# ProDocument_RFID-ARDUINO-FABLAB-BG_2024-.net
KiCad netlist of a schematic drawn in EasyEDA Pro
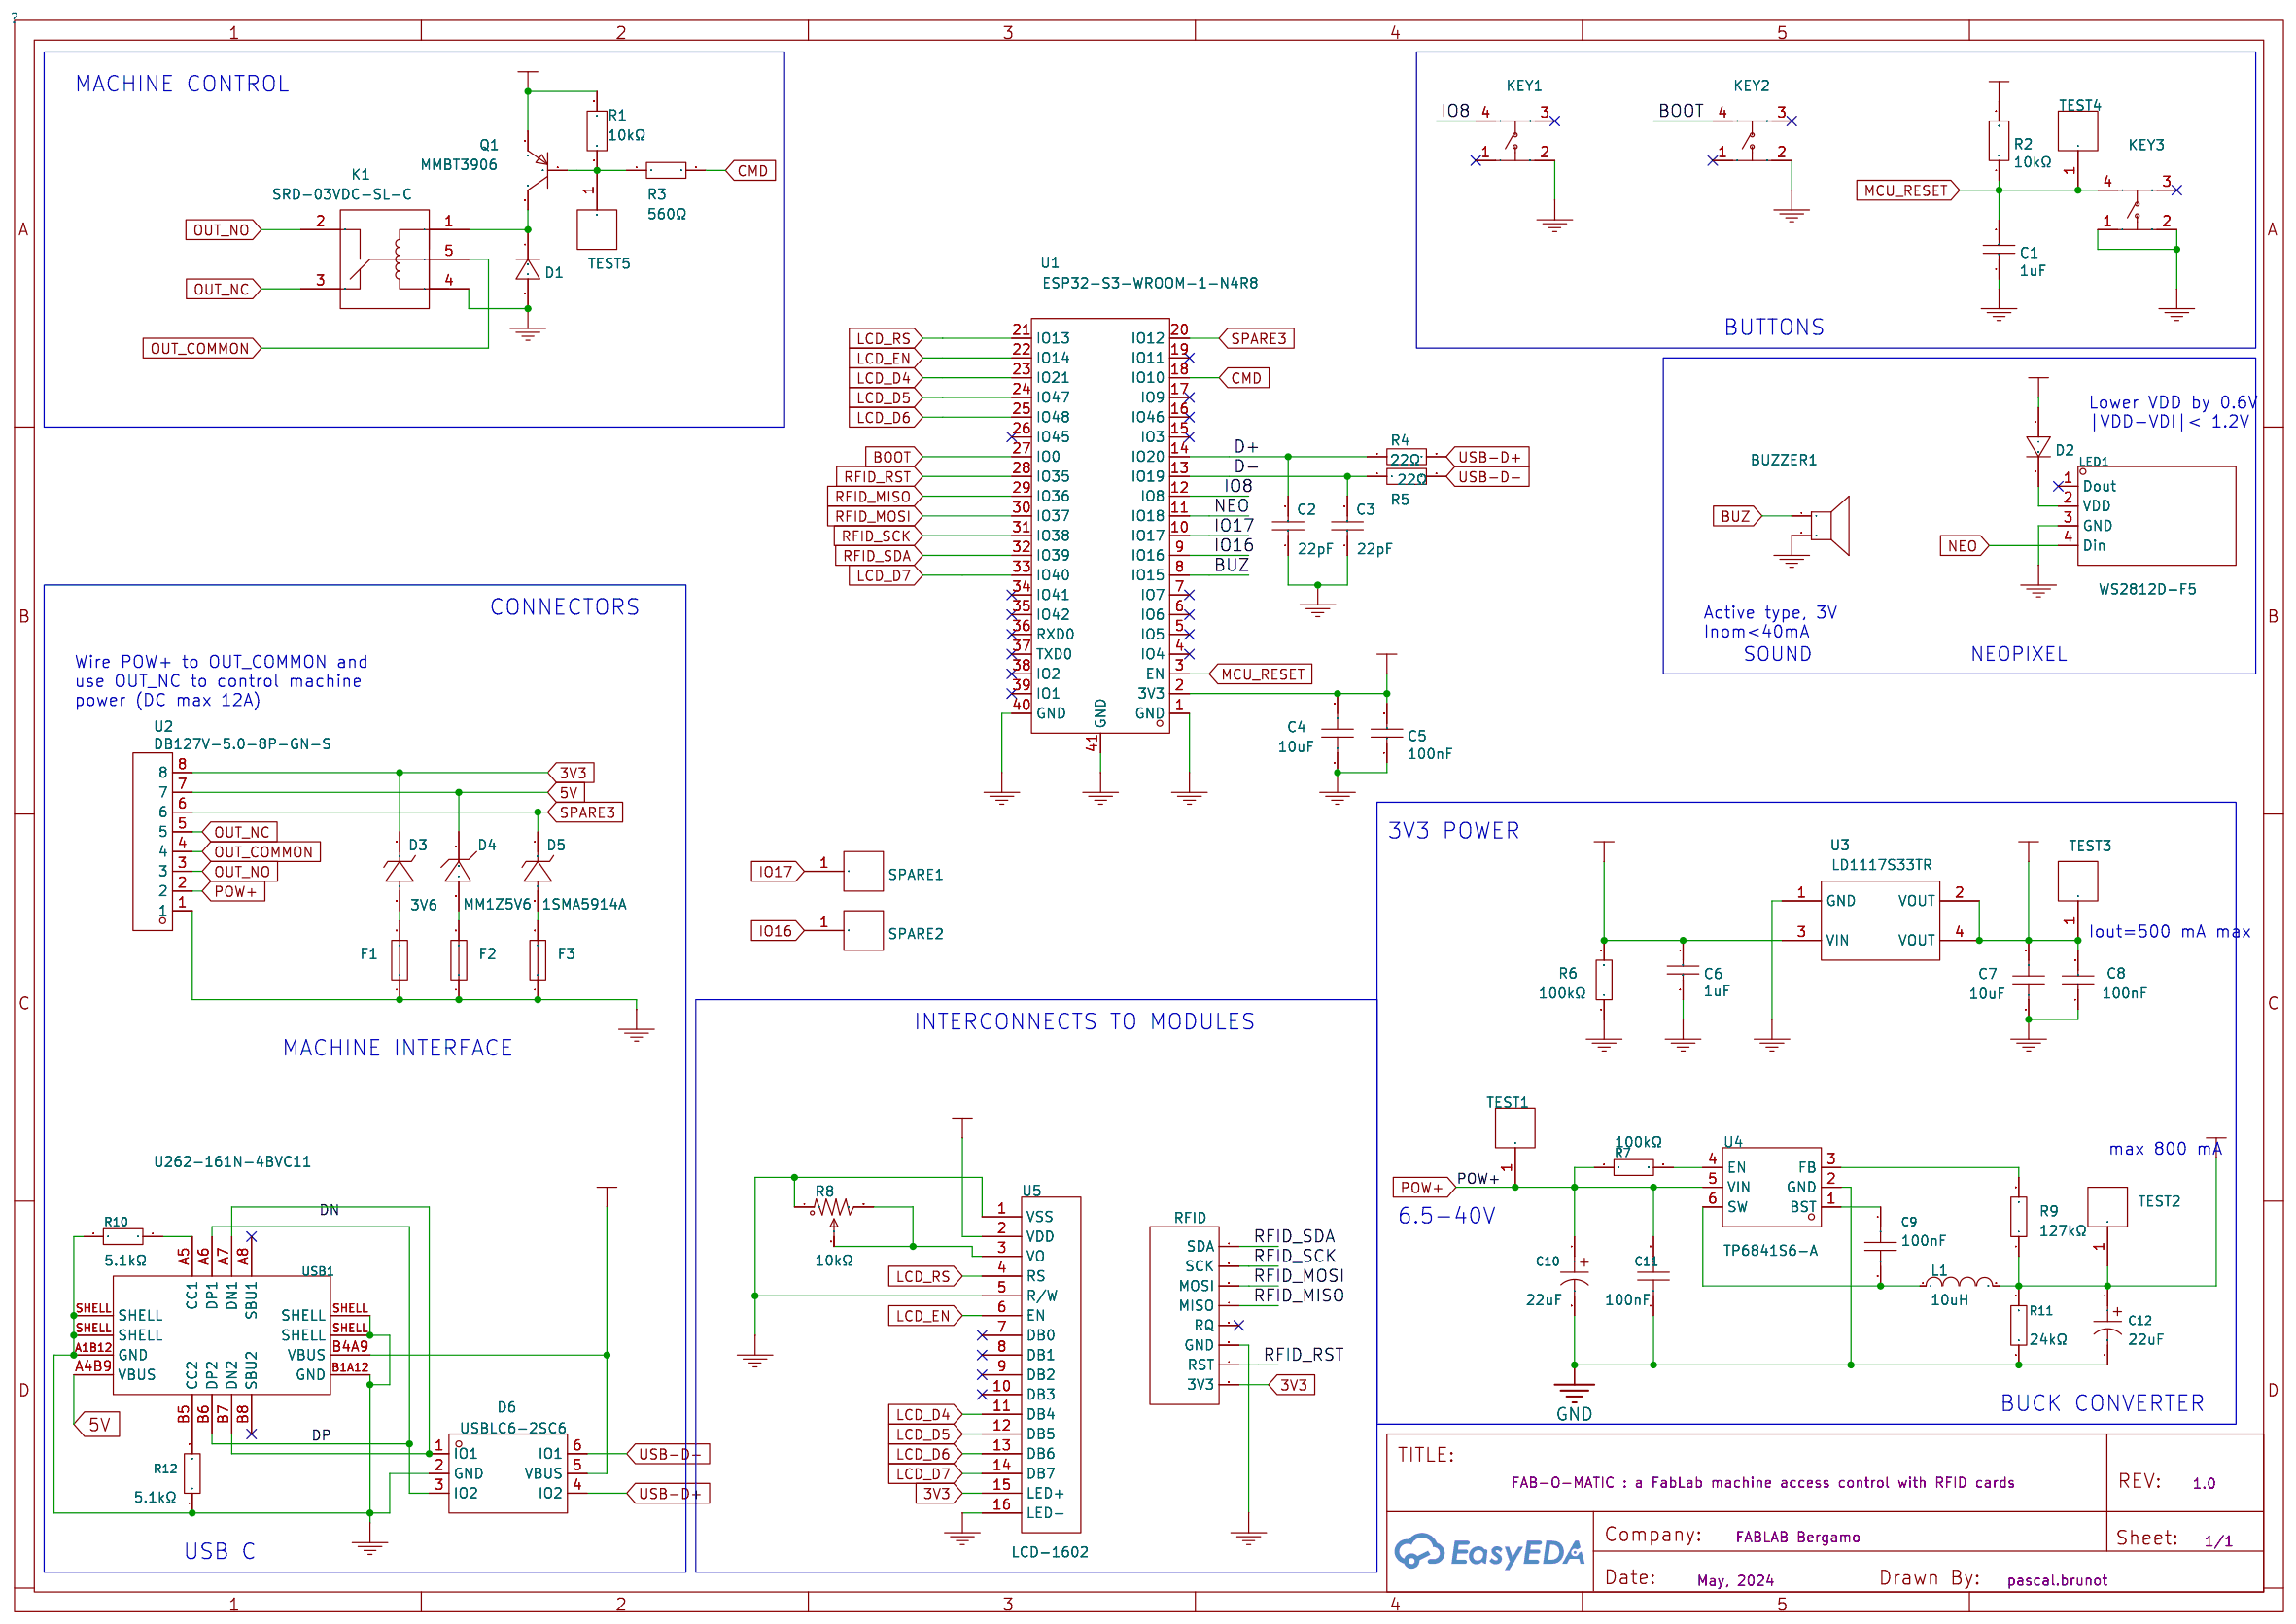
[diagram p0: schematic sheet]

(export (version "E")
  (design (tool "Eeschema 10.0.6"))
  (components
    (comp (ref "BUZZER1")
      (value "4kHz")
      (fields (field (name "Manufacturer Part") "SFN-12055PA6.5") (field (name "Manufacturer") "S&S(海旭)"))
      (libsource (lib "easyedapro") (part "4000Hz"))
    )
    (comp (ref "C1")
      (value "1uF")
      (fields
        (field (name "Manufacturer Part") "CL21B105KBFNNNE")
        (field (name "Manufacturer") "SAMSUNG(三星)")
      )
      (libsource (lib "easyedapro") (part "1uF"))
    )
    (comp (ref "C2")
      (value "22pF")
      (fields
        (field (name "Manufacturer Part") "CL10C220JB8NNNC")
        (field (name "Manufacturer") "SAMSUNG(三星)")
      )
      (libsource (lib "easyedapro") (part "22pF"))
    )
    (comp (ref "C3")
      (value "22pF")
      (fields
        (field (name "Manufacturer Part") "CL10C220JB8NNNC")
        (field (name "Manufacturer") "SAMSUNG(三星)")
      )
      (libsource (lib "easyedapro") (part "22pF"))
    )
    (comp (ref "C4")
      (value "10uF")
      (fields
        (field (name "Manufacturer Part") "GRM21BR61H106KE43L")
        (field (name "Manufacturer") "muRata(村田)")
      )
      (libsource (lib "easyedapro") (part "10uF"))
    )
    (comp (ref "C5")
      (value "100nF")
      (fields
        (field (name "Manufacturer Part") "CL21B104KCFNNNE")
        (field (name "Manufacturer") "SAMSUNG(三星)")
      )
      (libsource (lib "easyedapro") (part "100nF"))
    )
    (comp (ref "C6")
      (value "1uF")
      (fields
        (field (name "Manufacturer Part") "CL21B105KBFNNNE")
        (field (name "Manufacturer") "SAMSUNG(三星)")
      )
      (libsource (lib "easyedapro") (part "1uF"))
    )
    (comp (ref "C7")
      (value "10uF")
      (fields
        (field (name "Manufacturer Part") "GRM21BR61H106KE43L")
        (field (name "Manufacturer") "muRata(村田)")
      )
      (libsource (lib "easyedapro") (part "10uF"))
    )
    (comp (ref "C8")
      (value "100nF")
      (fields
        (field (name "Manufacturer Part") "CL21B104KCFNNNE")
        (field (name "Manufacturer") "SAMSUNG(三星)")
      )
      (libsource (lib "easyedapro") (part "100nF"))
    )
    (comp (ref "C9")
      (value "100nF")
      (footprint "easyedapro:C0603")
      (fields
        (field (name "Manufacturer Part") "CC0603KRX7R9BB104")
        (field (name "Manufacturer") "YAGEO(国巨)")
      )
      (libsource (lib "easyedapro") (part "CC0603KRX7R9BB104"))
    )
    (comp (ref "C10")
      (value "22uF")
      (footprint "easyedapro:CAP-SMD_BD6.3-L6.6-W6.6-FD")
      (fields
        (field (name "Manufacturer Part") "RVT22UF50V67RV0028")
        (field (name "Manufacturer") "KNSCHA(科尼盛)")
      )
      (libsource (lib "easyedapro") (part "RVT22UF50V67RV0028"))
    )
    (comp (ref "C11")
      (value "100nF")
      (footprint "easyedapro:C0603")
      (fields
        (field (name "Manufacturer Part") "CC0603KRX7R9BB104")
        (field (name "Manufacturer") "YAGEO(国巨)")
      )
      (libsource (lib "easyedapro") (part "CC0603KRX7R9BB104"))
    )
    (comp (ref "C12")
      (value "22uF")
      (footprint "easyedapro:CAP-SMD_BD6.3-L6.6-W6.6-FD")
      (fields
        (field (name "Manufacturer Part") "RVT22UF50V67RV0028")
        (field (name "Manufacturer") "KNSCHA(科尼盛)")
      )
      (libsource (lib "easyedapro") (part "RVT22UF50V67RV0028"))
    )
    (comp (ref "D1")
      (value "SM4007PL")
      (fields (field (name "Manufacturer") "MDD"))
      (libsource (lib "easyedapro") (part "SM4007PL"))
    )
    (comp (ref "D2")
      (value "SM4007PL")
      (fields (field (name "Manufacturer") "MDD"))
      (libsource (lib "easyedapro") (part "SM4007PL"))
    )
    (comp (ref "D3")
      (value "3V6")
      (fields (field (name "Manufacturer") "LGE(鲁光)"))
      (libsource (lib "easyedapro") (part "3V6"))
    )
    (comp (ref "D4")
      (value "MM1Z5V6")
      (fields (field (name "Manufacturer") "ST(先科)"))
      (libsource (lib "easyedapro") (part "5V6"))
    )
    (comp (ref "D5")
      (value "1SMA5914A")
      (fields (field (name "Manufacturer") "LGE(鲁光)"))
      (libsource (lib "easyedapro") (part "3V6"))
    )
    (comp (ref "D6")
      (value "USBLC6-2SC6")
      (fields (field (name "Manufacturer") "TECH PUBLIC(台舟)"))
      (libsource (lib "easyedapro") (part "USBLC6"))
    )
    (comp (ref "F1")
      (value "1206L016WR")
      (fields (field (name "Manufacturer") "Littelfuse(美国力特)"))
      (libsource (lib "easyedapro") (part "1206L016WR"))
    )
    (comp (ref "F2")
      (value "1206L016WR")
      (fields (field (name "Manufacturer") "Littelfuse(美国力特)"))
      (libsource (lib "easyedapro") (part "1206L016WR"))
    )
    (comp (ref "F3")
      (value "1206L016WR")
      (fields (field (name "Manufacturer") "Littelfuse(美国力特)"))
      (libsource (lib "easyedapro") (part "1206L016WR"))
    )
    (comp (ref "K1")
      (value "SRD-03VDC-SL-C")
      (fields (field (name "Manufacturer") "松乐"))
      (libsource (lib "easyedapro") (part "SRD-03VDC-SL-C_C496430"))
    )
    (comp (ref "KEY1")
      (value "TSA063G60-250")
      (footprint "easyedapro:KEY-SMD_4P-L6.1-W6.1-P4.50-LS9.0")
      (fields (field (name "Manufacturer") "BRIGHT(博瑞泰)"))
      (libsource (lib "easyedapro") (part "TSA063G60-250"))
    )
    (comp (ref "KEY2")
      (value "TSA063G60-250")
      (footprint "easyedapro:KEY-SMD_4P-L6.1-W6.1-P4.50-LS9.0")
      (fields (field (name "Manufacturer") "BRIGHT(博瑞泰)"))
      (libsource (lib "easyedapro") (part "TSA063G60-250"))
    )
    (comp (ref "KEY3")
      (value "TSA063G60-250")
      (footprint "easyedapro:KEY-SMD_4P-L6.1-W6.1-P4.50-LS9.0")
      (fields (field (name "Manufacturer") "BRIGHT(博瑞泰)"))
      (libsource (lib "easyedapro") (part "TSA063G60-250"))
    )
    (comp (ref "L1")
      (value "10uH")
      (footprint "easyedapro:IND-SMD_L4.0-W4.0")
      (fields (field (name "Manufacturer Part") "SWPA4030S100MT") (field (name "Manufacturer") "Sunlord(顺络)"))
      (libsource (lib "easyedapro") (part "SWPA4030S100MT"))
    )
    (comp (ref "LED1")
      (value "WS2812D-F5")
      (footprint "easyedapro:LED-TH_4P-BD5.8-P1.30")
      (description "Lamp Holder Type:5mm圆形灯头")
      (fields (field (name "Manufacturer") "worldsemi"))
      (libsource (lib "easyedapro") (part "WS2812D-F5"))
    )
    (comp (ref "P1")
      (value "RFID")
      (footprint "easyedapro:footprint_17af")
      (fields
        (field (name "Manufacturer Part") "Female headerHDR1X8-2.54")
        (field (name "Manufacturer") "BOOMELE")
      )
      (libsource (lib "easyedapro") (part "RFID"))
    )
    (comp (ref "Q1")
      (value "MMBT3906")
      (fields (field (name "Manufacturer") "High Diode(海德)"))
      (libsource (lib "easyedapro") (part "2N3906-AP"))
    )
    (comp (ref "R1")
      (value "10kΩ")
      (fields
        (field (name "Manufacturer Part") "0805W8F1002T5E")
        (field (name "Manufacturer") "UNI-ROYAL(厚声)")
      )
      (libsource (lib "easyedapro") (part "10k"))
    )
    (comp (ref "R2")
      (value "10kΩ")
      (fields
        (field (name "Manufacturer Part") "0805W8F1002T5E")
        (field (name "Manufacturer") "UNI-ROYAL(厚声)")
      )
      (libsource (lib "easyedapro") (part "10k"))
    )
    (comp (ref "R3")
      (value "560Ω")
      (fields
        (field (name "Manufacturer Part") "0805W8F5600T5E")
        (field (name "Manufacturer") "UNI-ROYAL(厚声)")
      )
      (libsource (lib "easyedapro") (part "560Ω"))
    )
    (comp (ref "R4")
      (value "22Ω")
      (fields
        (field (name "Manufacturer Part") "0603WAF220JT5E")
        (field (name "Manufacturer") "UNI-ROYAL(厚声)")
      )
      (libsource (lib "easyedapro") (part "22"))
    )
    (comp (ref "R5")
      (value "22Ω")
      (fields
        (field (name "Manufacturer Part") "0603WAF220JT5E")
        (field (name "Manufacturer") "UNI-ROYAL(厚声)")
      )
      (libsource (lib "easyedapro") (part "22"))
    )
    (comp (ref "R6")
      (value "100kΩ")
      (fields
        (field (name "Manufacturer Part") "0805W8F1003T5E")
        (field (name "Manufacturer") "UNI-ROYAL(厚声)")
      )
      (libsource (lib "easyedapro") (part "100kΩ"))
    )
    (comp (ref "R7")
      (value "100kΩ")
      (footprint "easyedapro:R0603")
      (fields
        (field (name "Manufacturer Part") "0603WAF1003T5E")
        (field (name "Manufacturer") "UNI-ROYAL(厚声)")
      )
      (libsource (lib "easyedapro") (part "0603WAF1003T5E"))
    )
    (comp (ref "R8")
      (value "10kΩ")
      (footprint "easyedapro:RES-ADJ-TH_3362P")
      (description "Resistance: Tolerance:±10% Tolerance:±10%")
      (fields (field (name "Manufacturer Part") "3362P-1-103") (field (name "Manufacturer") "BOCHEN(博晨)"))
      (libsource (lib "easyedapro") (part "3362P-1-103_C118956"))
    )
    (comp (ref "R9")
      (value "127kΩ")
      (footprint "easyedapro:R0603")
      (fields (field (name "Manufacturer Part") "RC0603FR-07127KL") (field (name "Manufacturer") "YAGEO(国巨)"))
      (libsource (lib "easyedapro") (part "RC0603FR-07127KL"))
    )
    (comp (ref "R10")
      (value "5.1kΩ")
      (footprint "easyedapro:R0603")
      (fields
        (field (name "Manufacturer Part") "0603WAF5101T5E")
        (field (name "Manufacturer") "UNI-ROYAL(厚声)")
      )
      (libsource (lib "easyedapro") (part "0603WAF5101T5E"))
    )
    (comp (ref "R11")
      (value "24kΩ")
      (footprint "easyedapro:R0603")
      (fields
        (field (name "Manufacturer Part") "0603WAF2402T5E")
        (field (name "Manufacturer") "UNI-ROYAL(厚声)")
      )
      (libsource (lib "easyedapro") (part "0603WAF2402T5E"))
    )
    (comp (ref "R12")
      (value "5.1kΩ")
      (footprint "easyedapro:R0603")
      (fields
        (field (name "Manufacturer Part") "0603WAF5101T5E")
        (field (name "Manufacturer") "UNI-ROYAL(厚声)")
      )
      (libsource (lib "easyedapro") (part "0603WAF5101T5E"))
    )
    (comp (ref "SPARE1")
      (value "0577-0-43-80-21-27-10-0")
      (footprint "easyedapro:footprint_662d")
      (libsource (lib "easyedapro") (part "0577-0-43-80-21-27-10-0"))
    )
    (comp (ref "SPARE2")
      (value "0577-0-43-80-21-27-10-0")
      (footprint "easyedapro:footprint_662d")
      (libsource (lib "easyedapro") (part "0577-0-43-80-21-27-10-0"))
    )
    (comp (ref "TEST1")
      (value "0577-0-43-80-21-27-10-0")
      (footprint "easyedapro:footprint_662d")
      (libsource (lib "easyedapro") (part "0577-0-43-80-21-27-10-0"))
    )
    (comp (ref "TEST2")
      (value "0577-0-43-80-21-27-10-0")
      (footprint "easyedapro:footprint_662d")
      (libsource (lib "easyedapro") (part "0577-0-43-80-21-27-10-0"))
    )
    (comp (ref "TEST3")
      (value "0577-0-43-80-21-27-10-0")
      (footprint "easyedapro:footprint_662d")
      (libsource (lib "easyedapro") (part "0577-0-43-80-21-27-10-0"))
    )
    (comp (ref "TEST4")
      (value "0577-0-43-80-21-27-10-0")
      (footprint "easyedapro:footprint_662d")
      (libsource (lib "easyedapro") (part "0577-0-43-80-21-27-10-0"))
    )
    (comp (ref "TEST5")
      (value "0577-0-43-80-21-27-10-0")
      (footprint "easyedapro:footprint_662d")
      (libsource (lib "easyedapro") (part "0577-0-43-80-21-27-10-0"))
    )
    (comp (ref "U1")
      (value "ESP32-S3-WROOM-1-N4R8")
      (fields (field (name "Manufacturer") "ESPRESSIF(乐鑫)"))
      (libsource (lib "easyedapro") (part "ESP32-S3-WROOM-1-N4"))
    )
    (comp (ref "U2")
      (value "DB127V-5.0-8P-GN-S")
      (fields (field (name "Manufacturer") "DORABO(地博电气)"))
      (libsource (lib "easyedapro") (part "DB127V-5.0-8P-GN-S"))
    )
    (comp (ref "U3")
      (value "LD1117S33TR")
      (fields (field (name "Manufacturer") "ST(意法半导体)"))
      (libsource (lib "easyedapro") (part "LD1117S33TR"))
    )
    (comp (ref "U4")
      (value "TP6841S6-A")
      (footprint "easyedapro:SOT-23-6_L2.9-W1.6-P0.95-LS2.8-BL")
      (fields (field (name "Manufacturer") "TECH PUBLIC(台舟)"))
      (libsource (lib "easyedapro") (part "TP6841S6-A"))
    )
    (comp (ref "U5")
      (value "LCD-1602")
      (footprint "easyedapro:footprint_8a57")
      (fields (field (name "Manufacturer Part") "?"))
      (libsource (lib "easyedapro") (part "LCD-1602"))
    )
    (comp (ref "USB1")
      (value "U262-161N-4BVC11")
      (footprint "easyedapro:USB-3.1-SMD_U262-161N-4BVC11")
      (fields (field (name "Manufacturer") "XKB Connectivity(中国星坤)"))
      (libsource (lib "easyedapro") (part "U262-16XN-4BVC11"))
    )
  )
  (nets
    (net (code "1") (name "/D+") (class "Default")
      (node (ref "C2") (pin "2") (pinfunction "2_2") (pintype "input"))
      (node (ref "R4") (pin "1") (pinfunction "1_1") (pintype "input"))
      (node (ref "U1") (pin "14") (pinfunction "IO20_14") (pintype "unspecified"))
    )
    (net (code "2") (name "/D-") (class "Default")
      (node (ref "C3") (pin "2") (pinfunction "2_2") (pintype "input"))
      (node (ref "R5") (pin "1") (pinfunction "1_1") (pintype "input"))
      (node (ref "U1") (pin "13") (pinfunction "IO19_13") (pintype "unspecified"))
    )
    (net (code "3") (name "/DN") (class "Default")
      (node (ref "D6") (pin "1") (pinfunction "IO1_1") (pintype "unspecified"))
      (node (ref "USB1") (pin "A7") (pinfunction "DN1_A7") (pintype "input"))
      (node (ref "USB1") (pin "B7") (pinfunction "DN2_B7") (pintype "input"))
    )
    (net (code "4") (name "/DP") (class "Default")
      (node (ref "D6") (pin "3") (pinfunction "IO2_3") (pintype "unspecified"))
      (node (ref "USB1") (pin "A6") (pinfunction "DP1_A6") (pintype "input"))
      (node (ref "USB1") (pin "B6") (pinfunction "DP2_B6") (pintype "input"))
    )
    (net (code "5") (name "/IO8") (class "Default")
      (node (ref "KEY1") (pin "4") (pinfunction "4_4") (pintype "input"))
      (node (ref "U1") (pin "12") (pinfunction "IO8_12") (pintype "unspecified"))
    )
    (net (code "6") (name "3V3") (class "Default")
      (node (ref "C4") (pin "2") (pinfunction "2_2") (pintype "unspecified"))
      (node (ref "C5") (pin "2") (pinfunction "2_2") (pintype "input"))
      (node (ref "C7") (pin "2") (pinfunction "2_2") (pintype "unspecified"))
      (node (ref "C8") (pin "2") (pinfunction "2_2") (pintype "input"))
      (node (ref "D3") (pin "1") (pinfunction "C_1") (pintype "unspecified"))
      (node (ref "P1") (pin "8") (pinfunction "3V3_8") (pintype "input"))
      (node (ref "Q1") (pin "1") (pinfunction "1_1") (pintype "input"))
      (node (ref "R1") (pin "2") (pinfunction "2_2") (pintype "unspecified"))
      (node (ref "R2") (pin "2") (pinfunction "2_2") (pintype "unspecified"))
      (node (ref "TEST3") (pin "1") (pinfunction "1_1") (pintype "unspecified"))
      (node (ref "U1") (pin "2") (pinfunction "3V3_2") (pintype "unspecified"))
      (node (ref "U2") (pin "8") (pinfunction "8_8") (pintype "unspecified"))
      (node (ref "U3") (pin "2") (pinfunction "VOUT_2") (pintype "unspecified"))
      (node (ref "U3") (pin "4") (pinfunction "VOUT_4") (pintype "unspecified"))
      (node (ref "U5") (pin "15") (pinfunction "LED+_15") (pintype "unspecified"))
    )
    (net (code "7") (name "5V") (class "Default")
      (node (ref "C12") (pin "1") (pinfunction "1_1") (pintype "input"))
      (node (ref "C6") (pin "1") (pinfunction "1_1") (pintype "input"))
      (node (ref "D2") (pin "2") (pinfunction "A_2") (pintype "unspecified"))
      (node (ref "D4") (pin "1") (pinfunction "C_1") (pintype "unspecified"))
      (node (ref "D6") (pin "5") (pinfunction "VBUS_5") (pintype "unspecified"))
      (node (ref "L1") (pin "2") (pinfunction "2_2") (pintype "input"))
      (node (ref "R11") (pin "2") (pinfunction "2_2") (pintype "input"))
      (node (ref "R6") (pin "2") (pinfunction "2_2") (pintype "unspecified"))
      (node (ref "R9") (pin "1") (pinfunction "1_1") (pintype "unspecified"))
      (node (ref "TEST2") (pin "1") (pinfunction "1_1") (pintype "unspecified"))
      (node (ref "U2") (pin "7") (pinfunction "7_7") (pintype "unspecified"))
      (node (ref "U3") (pin "3") (pinfunction "VIN_3") (pintype "unspecified"))
      (node (ref "U5") (pin "2") (pinfunction "VDD_2") (pintype "unspecified"))
      (node (ref "USB1") (pin "A4B9") (pinfunction "VBUS_A4B9") (pintype "input"))
      (node (ref "USB1") (pin "B4A9") (pinfunction "VBUS_B4A9") (pintype "input"))
    )
    (net (code "8") (name "BOOT") (class "Default")
      (node (ref "KEY2") (pin "4") (pinfunction "4_4") (pintype "input"))
      (node (ref "U1") (pin "27") (pinfunction "IO0_27") (pintype "unspecified"))
    )
    (net (code "9") (name "BUZ") (class "Default")
      (node (ref "BUZZER1") (pin "1") (pinfunction "1_1") (pintype "unspecified"))
      (node (ref "U1") (pin "8") (pinfunction "IO15_8") (pintype "unspecified"))
    )
    (net (code "10") (name "CMD") (class "Default")
      (node (ref "R3") (pin "2") (pinfunction "2_2") (pintype "input"))
      (node (ref "U1") (pin "18") (pinfunction "IO10_18") (pintype "unspecified"))
    )
    (net (code "11") (name "GND") (class "Default")
      (node (ref "BUZZER1") (pin "2") (pinfunction "2_2") (pintype "unspecified"))
      (node (ref "C1") (pin "1") (pinfunction "1_1") (pintype "input"))
      (node (ref "C10") (pin "2") (pinfunction "2_2") (pintype "input"))
      (node (ref "C11") (pin "1") (pinfunction "1_1") (pintype "input"))
      (node (ref "C12") (pin "2") (pinfunction "2_2") (pintype "input"))
      (node (ref "C2") (pin "1") (pinfunction "1_1") (pintype "input"))
      (node (ref "C3") (pin "1") (pinfunction "1_1") (pintype "input"))
      (node (ref "C4") (pin "1") (pinfunction "1_1") (pintype "unspecified"))
      (node (ref "C5") (pin "1") (pinfunction "1_1") (pintype "input"))
      (node (ref "C6") (pin "2") (pinfunction "2_2") (pintype "input"))
      (node (ref "C7") (pin "1") (pinfunction "1_1") (pintype "unspecified"))
      (node (ref "C8") (pin "1") (pinfunction "1_1") (pintype "input"))
      (node (ref "D1") (pin "2") (pinfunction "A_2") (pintype "unspecified"))
      (node (ref "D6") (pin "2") (pinfunction "GND_2") (pintype "unspecified"))
      (node (ref "F1") (pin "1") (pinfunction "1_1") (pintype "unspecified"))
      (node (ref "F2") (pin "1") (pinfunction "1_1") (pintype "unspecified"))
      (node (ref "F3") (pin "1") (pinfunction "1_1") (pintype "unspecified"))
      (node (ref "K1") (pin "4") (pinfunction "4_4") (pintype "unspecified"))
      (node (ref "KEY1") (pin "2") (pinfunction "2_2") (pintype "input"))
      (node (ref "KEY2") (pin "2") (pinfunction "2_2") (pintype "input"))
      (node (ref "KEY3") (pin "1") (pinfunction "1_1") (pintype "input"))
      (node (ref "KEY3") (pin "2") (pinfunction "2_2") (pintype "input"))
      (node (ref "LED1") (pin "3") (pinfunction "GND_3") (pintype "input"))
      (node (ref "P1") (pin "6") (pinfunction "GND_6") (pintype "input"))
      (node (ref "R10") (pin "2") (pinfunction "2_2") (pintype "input"))
      (node (ref "R11") (pin "1") (pinfunction "1_1") (pintype "input"))
      (node (ref "R12") (pin "1") (pinfunction "1_1") (pintype "input"))
      (node (ref "R6") (pin "1") (pinfunction "1_1") (pintype "unspecified"))
      (node (ref "R8") (pin "1") (pinfunction "1_1") (pintype "input"))
      (node (ref "U1") (pin "1") (pinfunction "GND_1") (pintype "unspecified"))
      (node (ref "U1") (pin "40") (pinfunction "GND_40") (pintype "unspecified"))
      (node (ref "U1") (pin "41") (pinfunction "GND_41") (pintype "unspecified"))
      (node (ref "U2") (pin "1") (pinfunction "1_1") (pintype "unspecified"))
      (node (ref "U3") (pin "1") (pinfunction "GND_1") (pintype "unspecified"))
      (node (ref "U4") (pin "2") (pinfunction "GND_2") (pintype "input"))
      (node (ref "U5") (pin "1") (pinfunction "VSS_1") (pintype "unspecified"))
      (node (ref "U5") (pin "16") (pinfunction "LED-_16") (pintype "unspecified"))
      (node (ref "U5") (pin "5") (pinfunction "R/W_5") (pintype "unspecified"))
      (node (ref "USB1") (pin "A1B12") (pinfunction "GND_A1B12") (pintype "input"))
      (node (ref "USB1") (pin "B1A12") (pinfunction "GND_B1A12") (pintype "input"))
      (node (ref "USB1") (pin "SHELL") (pinfunction "SHELL_SHELL") (pintype "input"))
    )
    (net (code "12") (name "IO16") (class "Default")
      (node (ref "SPARE2") (pin "1") (pinfunction "1_1") (pintype "unspecified"))
      (node (ref "U1") (pin "9") (pinfunction "IO16_9") (pintype "unspecified"))
    )
    (net (code "13") (name "IO17") (class "Default")
      (node (ref "SPARE1") (pin "1") (pinfunction "1_1") (pintype "unspecified"))
      (node (ref "U1") (pin "10") (pinfunction "IO17_10") (pintype "unspecified"))
    )
    (net (code "14") (name "LCD_D4") (class "Default")
      (node (ref "U1") (pin "23") (pinfunction "IO21_23") (pintype "unspecified"))
      (node (ref "U5") (pin "11") (pinfunction "DB4_11") (pintype "unspecified"))
    )
    (net (code "15") (name "LCD_D5") (class "Default")
      (node (ref "U1") (pin "24") (pinfunction "IO47_24") (pintype "unspecified"))
      (node (ref "U5") (pin "12") (pinfunction "DB5_12") (pintype "unspecified"))
    )
    (net (code "16") (name "LCD_D6") (class "Default")
      (node (ref "U1") (pin "25") (pinfunction "IO48_25") (pintype "unspecified"))
      (node (ref "U5") (pin "13") (pinfunction "DB6_13") (pintype "unspecified"))
    )
    (net (code "17") (name "LCD_D7") (class "Default")
      (node (ref "U1") (pin "33") (pinfunction "IO40_33") (pintype "unspecified"))
      (node (ref "U5") (pin "14") (pinfunction "DB7_14") (pintype "unspecified"))
    )
    (net (code "18") (name "LCD_EN") (class "Default")
      (node (ref "U1") (pin "22") (pinfunction "IO14_22") (pintype "unspecified"))
      (node (ref "U5") (pin "6") (pinfunction "EN_6") (pintype "unspecified"))
    )
    (net (code "19") (name "LCD_RS") (class "Default")
      (node (ref "U1") (pin "21") (pinfunction "IO13_21") (pintype "unspecified"))
      (node (ref "U5") (pin "4") (pinfunction "RS_4") (pintype "unspecified"))
    )
    (net (code "20") (name "MCU_RESET") (class "Default")
      (node (ref "C1") (pin "2") (pinfunction "2_2") (pintype "input"))
      (node (ref "KEY3") (pin "4") (pinfunction "4_4") (pintype "input"))
      (node (ref "R2") (pin "1") (pinfunction "1_1") (pintype "unspecified"))
      (node (ref "TEST4") (pin "1") (pinfunction "1_1") (pintype "unspecified"))
      (node (ref "U1") (pin "3") (pinfunction "EN_3") (pintype "unspecified"))
    )
    (net (code "21") (name "NEO") (class "Default")
      (node (ref "LED1") (pin "4") (pinfunction "Din_4") (pintype "input"))
      (node (ref "U1") (pin "11") (pinfunction "IO18_11") (pintype "unspecified"))
    )
    (net (code "22") (name "Net-(D1-C)") (class "Default")
      (node (ref "D1") (pin "1") (pinfunction "C_1") (pintype "unspecified"))
      (node (ref "K1") (pin "1") (pinfunction "1_1") (pintype "unspecified"))
      (node (ref "Q1") (pin "3") (pinfunction "3_3") (pintype "input"))
    )
    (net (code "23") (name "Net-(D2-C)") (class "Default")
      (node (ref "D2") (pin "1") (pinfunction "C_1") (pintype "unspecified"))
      (node (ref "LED1") (pin "2") (pinfunction "VDD_2") (pintype "input"))
    )
    (net (code "24") (name "Net-(D3-A)") (class "Default")
      (node (ref "D3") (pin "2") (pinfunction "A_2") (pintype "unspecified"))
      (node (ref "F1") (pin "2") (pinfunction "2_2") (pintype "unspecified"))
    )
    (net (code "25") (name "Net-(D4-A)") (class "Default")
      (node (ref "D4") (pin "2") (pinfunction "A_2") (pintype "unspecified"))
      (node (ref "F2") (pin "2") (pinfunction "2_2") (pintype "unspecified"))
    )
    (net (code "26") (name "Net-(D5-A)") (class "Default")
      (node (ref "D5") (pin "2") (pinfunction "A_2") (pintype "unspecified"))
      (node (ref "F3") (pin "2") (pinfunction "2_2") (pintype "unspecified"))
    )
    (net (code "27") (name "Net-(Q1-Pad2)") (class "Default")
      (node (ref "Q1") (pin "2") (pinfunction "2_2") (pintype "input"))
      (node (ref "R1") (pin "1") (pinfunction "1_1") (pintype "unspecified"))
      (node (ref "R3") (pin "1") (pinfunction "1_1") (pintype "input"))
      (node (ref "TEST5") (pin "1") (pinfunction "1_1") (pintype "unspecified"))
    )
    (net (code "28") (name "Net-(U4-BST)") (class "Default")
      (node (ref "C9") (pin "1") (pinfunction "1_1") (pintype "input"))
      (node (ref "U4") (pin "1") (pinfunction "BST_1") (pintype "input"))
    )
    (net (code "29") (name "Net-(U4-EN)") (class "Default")
      (node (ref "R7") (pin "2") (pinfunction "2_2") (pintype "input"))
      (node (ref "U4") (pin "4") (pinfunction "EN_4") (pintype "input"))
    )
    (net (code "30") (name "Net-(U4-FB)") (class "Default")
      (node (ref "R9") (pin "2") (pinfunction "2_2") (pintype "unspecified"))
      (node (ref "U4") (pin "3") (pinfunction "FB_3") (pintype "input"))
    )
    (net (code "31") (name "Net-(U4-SW)") (class "Default")
      (node (ref "C9") (pin "2") (pinfunction "2_2") (pintype "input"))
      (node (ref "L1") (pin "1") (pinfunction "1_1") (pintype "input"))
      (node (ref "U4") (pin "6") (pinfunction "SW_6") (pintype "input"))
    )
    (net (code "32") (name "Net-(U5-VO)") (class "Default")
      (node (ref "R8") (pin "2") (pinfunction "2_2") (pintype "input"))
      (node (ref "R8") (pin "3") (pinfunction "3_3") (pintype "input"))
      (node (ref "U5") (pin "3") (pinfunction "VO_3") (pintype "unspecified"))
    )
    (net (code "33") (name "Net-(USB1-CC1)") (class "Default")
      (node (ref "R10") (pin "1") (pinfunction "1_1") (pintype "input"))
      (node (ref "USB1") (pin "A5") (pinfunction "CC1_A5") (pintype "input"))
    )
    (net (code "34") (name "Net-(USB1-CC2)") (class "Default")
      (node (ref "R12") (pin "2") (pinfunction "2_2") (pintype "input"))
      (node (ref "USB1") (pin "B5") (pinfunction "CC2_B5") (pintype "input"))
    )
    (net (code "35") (name "OUT_COMMON") (class "Default")
      (node (ref "K1") (pin "5") (pinfunction "5_5") (pintype "unspecified"))
      (node (ref "U2") (pin "4") (pinfunction "4_4") (pintype "unspecified"))
    )
    (net (code "36") (name "OUT_NC") (class "Default")
      (node (ref "K1") (pin "3") (pinfunction "3_3") (pintype "unspecified"))
      (node (ref "U2") (pin "5") (pinfunction "5_5") (pintype "unspecified"))
    )
    (net (code "37") (name "OUT_NO") (class "Default")
      (node (ref "K1") (pin "2") (pinfunction "2_2") (pintype "unspecified"))
      (node (ref "U2") (pin "3") (pinfunction "3_3") (pintype "unspecified"))
    )
    (net (code "38") (name "POW+") (class "Default")
      (node (ref "C10") (pin "1") (pinfunction "1_1") (pintype "input"))
      (node (ref "C11") (pin "2") (pinfunction "2_2") (pintype "input"))
      (node (ref "R7") (pin "1") (pinfunction "1_1") (pintype "input"))
      (node (ref "TEST1") (pin "1") (pinfunction "1_1") (pintype "unspecified"))
      (node (ref "U2") (pin "2") (pinfunction "2_2") (pintype "unspecified"))
      (node (ref "U4") (pin "5") (pinfunction "VIN_5") (pintype "input"))
    )
    (net (code "39") (name "RFID_MISO") (class "Default")
      (node (ref "P1") (pin "4") (pinfunction "MISO_4") (pintype "input"))
      (node (ref "U1") (pin "29") (pinfunction "IO36_29") (pintype "unspecified"))
    )
    (net (code "40") (name "RFID_MOSI") (class "Default")
      (node (ref "P1") (pin "3") (pinfunction "MOSI_3") (pintype "input"))
      (node (ref "U1") (pin "30") (pinfunction "IO37_30") (pintype "unspecified"))
    )
    (net (code "41") (name "RFID_RST") (class "Default")
      (node (ref "P1") (pin "7") (pinfunction "RST_7") (pintype "input"))
      (node (ref "U1") (pin "28") (pinfunction "IO35_28") (pintype "unspecified"))
    )
    (net (code "42") (name "RFID_SCK") (class "Default")
      (node (ref "P1") (pin "2") (pinfunction "SCK_2") (pintype "input"))
      (node (ref "U1") (pin "31") (pinfunction "IO38_31") (pintype "unspecified"))
    )
    (net (code "43") (name "RFID_SDA") (class "Default")
      (node (ref "P1") (pin "1") (pinfunction "SDA_1") (pintype "input"))
      (node (ref "U1") (pin "32") (pinfunction "IO39_32") (pintype "unspecified"))
    )
    (net (code "44") (name "SPARE3") (class "Default")
      (node (ref "D5") (pin "1") (pinfunction "C_1") (pintype "unspecified"))
      (node (ref "U1") (pin "20") (pinfunction "IO12_20") (pintype "unspecified"))
      (node (ref "U2") (pin "6") (pinfunction "6_6") (pintype "unspecified"))
    )
    (net (code "45") (name "USB-D+") (class "Default")
      (node (ref "D6") (pin "4") (pinfunction "IO2_4") (pintype "unspecified"))
      (node (ref "R4") (pin "2") (pinfunction "2_2") (pintype "input"))
    )
    (net (code "46") (name "USB-D-") (class "Default")
      (node (ref "D6") (pin "6") (pinfunction "IO1_6") (pintype "unspecified"))
      (node (ref "R5") (pin "2") (pinfunction "2_2") (pintype "input"))
    )
    (net (code "47") (name "unconnected-(KEY1-Pad1)") (class "Default")
      (node (ref "KEY1") (pin "1") (pinfunction "1_1") (pintype "input+no_connect"))
    )
    (net (code "48") (name "unconnected-(KEY1-Pad3)") (class "Default")
      (node (ref "KEY1") (pin "3") (pinfunction "3_3") (pintype "input+no_connect"))
    )
    (net (code "49") (name "unconnected-(KEY2-Pad1)") (class "Default")
      (node (ref "KEY2") (pin "1") (pinfunction "1_1") (pintype "input+no_connect"))
    )
    (net (code "50") (name "unconnected-(KEY2-Pad3)") (class "Default")
      (node (ref "KEY2") (pin "3") (pinfunction "3_3") (pintype "input+no_connect"))
    )
    (net (code "51") (name "unconnected-(KEY3-Pad3)") (class "Default")
      (node (ref "KEY3") (pin "3") (pinfunction "3_3") (pintype "input+no_connect"))
    )
    (net (code "52") (name "unconnected-(LED1-Dout-Pad1)") (class "Default")
      (node (ref "LED1") (pin "1") (pinfunction "Dout_1") (pintype "input+no_connect"))
    )
    (net (code "53") (name "unconnected-(P1-RQ-Pad5)") (class "Default")
      (node (ref "P1") (pin "5") (pinfunction "RQ_5") (pintype "input+no_connect"))
    )
    (net (code "54") (name "unconnected-(U1-IO1-Pad39)") (class "Default")
      (node (ref "U1") (pin "39") (pinfunction "IO1_39") (pintype "unspecified+no_connect"))
    )
    (net (code "55") (name "unconnected-(U1-IO2-Pad38)") (class "Default")
      (node (ref "U1") (pin "38") (pinfunction "IO2_38") (pintype "unspecified+no_connect"))
    )
    (net (code "56") (name "unconnected-(U1-IO3-Pad15)") (class "Default")
      (node (ref "U1") (pin "15") (pinfunction "IO3_15") (pintype "unspecified+no_connect"))
    )
    (net (code "57") (name "unconnected-(U1-IO4-Pad4)") (class "Default")
      (node (ref "U1") (pin "4") (pinfunction "IO4_4") (pintype "unspecified+no_connect"))
    )
    (net (code "58") (name "unconnected-(U1-IO5-Pad5)") (class "Default")
      (node (ref "U1") (pin "5") (pinfunction "IO5_5") (pintype "unspecified+no_connect"))
    )
    (net (code "59") (name "unconnected-(U1-IO6-Pad6)") (class "Default")
      (node (ref "U1") (pin "6") (pinfunction "IO6_6") (pintype "unspecified+no_connect"))
    )
    (net (code "60") (name "unconnected-(U1-IO7-Pad7)") (class "Default")
      (node (ref "U1") (pin "7") (pinfunction "IO7_7") (pintype "unspecified+no_connect"))
    )
    (net (code "61") (name "unconnected-(U1-IO9-Pad17)") (class "Default")
      (node (ref "U1") (pin "17") (pinfunction "IO9_17") (pintype "unspecified+no_connect"))
    )
    (net (code "62") (name "unconnected-(U1-IO11-Pad19)") (class "Default")
      (node (ref "U1") (pin "19") (pinfunction "IO11_19") (pintype "unspecified+no_connect"))
    )
    (net (code "63") (name "unconnected-(U1-IO41-Pad34)") (class "Default")
      (node (ref "U1") (pin "34") (pinfunction "IO41_34") (pintype "unspecified+no_connect"))
    )
    (net (code "64") (name "unconnected-(U1-IO42-Pad35)") (class "Default")
      (node (ref "U1") (pin "35") (pinfunction "IO42_35") (pintype "unspecified+no_connect"))
    )
    (net (code "65") (name "unconnected-(U1-IO45-Pad26)") (class "Default")
      (node (ref "U1") (pin "26") (pinfunction "IO45_26") (pintype "unspecified+no_connect"))
    )
    (net (code "66") (name "unconnected-(U1-IO46-Pad16)") (class "Default")
      (node (ref "U1") (pin "16") (pinfunction "IO46_16") (pintype "unspecified+no_connect"))
    )
    (net (code "67") (name "unconnected-(U1-RXD0-Pad36)") (class "Default")
      (node (ref "U1") (pin "36") (pinfunction "RXD0_36") (pintype "unspecified+no_connect"))
    )
    (net (code "68") (name "unconnected-(U1-TXD0-Pad37)") (class "Default")
      (node (ref "U1") (pin "37") (pinfunction "TXD0_37") (pintype "unspecified+no_connect"))
    )
    (net (code "69") (name "unconnected-(U5-DB0-Pad7)") (class "Default")
      (node (ref "U5") (pin "7") (pinfunction "DB0_7") (pintype "unspecified+no_connect"))
    )
    (net (code "70") (name "unconnected-(U5-DB1-Pad8)") (class "Default")
      (node (ref "U5") (pin "8") (pinfunction "DB1_8") (pintype "unspecified+no_connect"))
    )
    (net (code "71") (name "unconnected-(U5-DB2-Pad9)") (class "Default")
      (node (ref "U5") (pin "9") (pinfunction "DB2_9") (pintype "unspecified+no_connect"))
    )
    (net (code "72") (name "unconnected-(U5-DB3-Pad10)") (class "Default")
      (node (ref "U5") (pin "10") (pinfunction "DB3_10") (pintype "unspecified+no_connect"))
    )
    (net (code "73") (name "unconnected-(USB1-SBU1-PadA8)") (class "Default")
      (node (ref "USB1") (pin "A8") (pinfunction "SBU1_A8") (pintype "input+no_connect"))
    )
    (net (code "74") (name "unconnected-(USB1-SBU2-PadB8)") (class "Default")
      (node (ref "USB1") (pin "B8") (pinfunction "SBU2_B8") (pintype "input+no_connect"))
    )
  )
)
